# tracker03-09.net
KiCad netlist of a schematic drawn in EAGLE
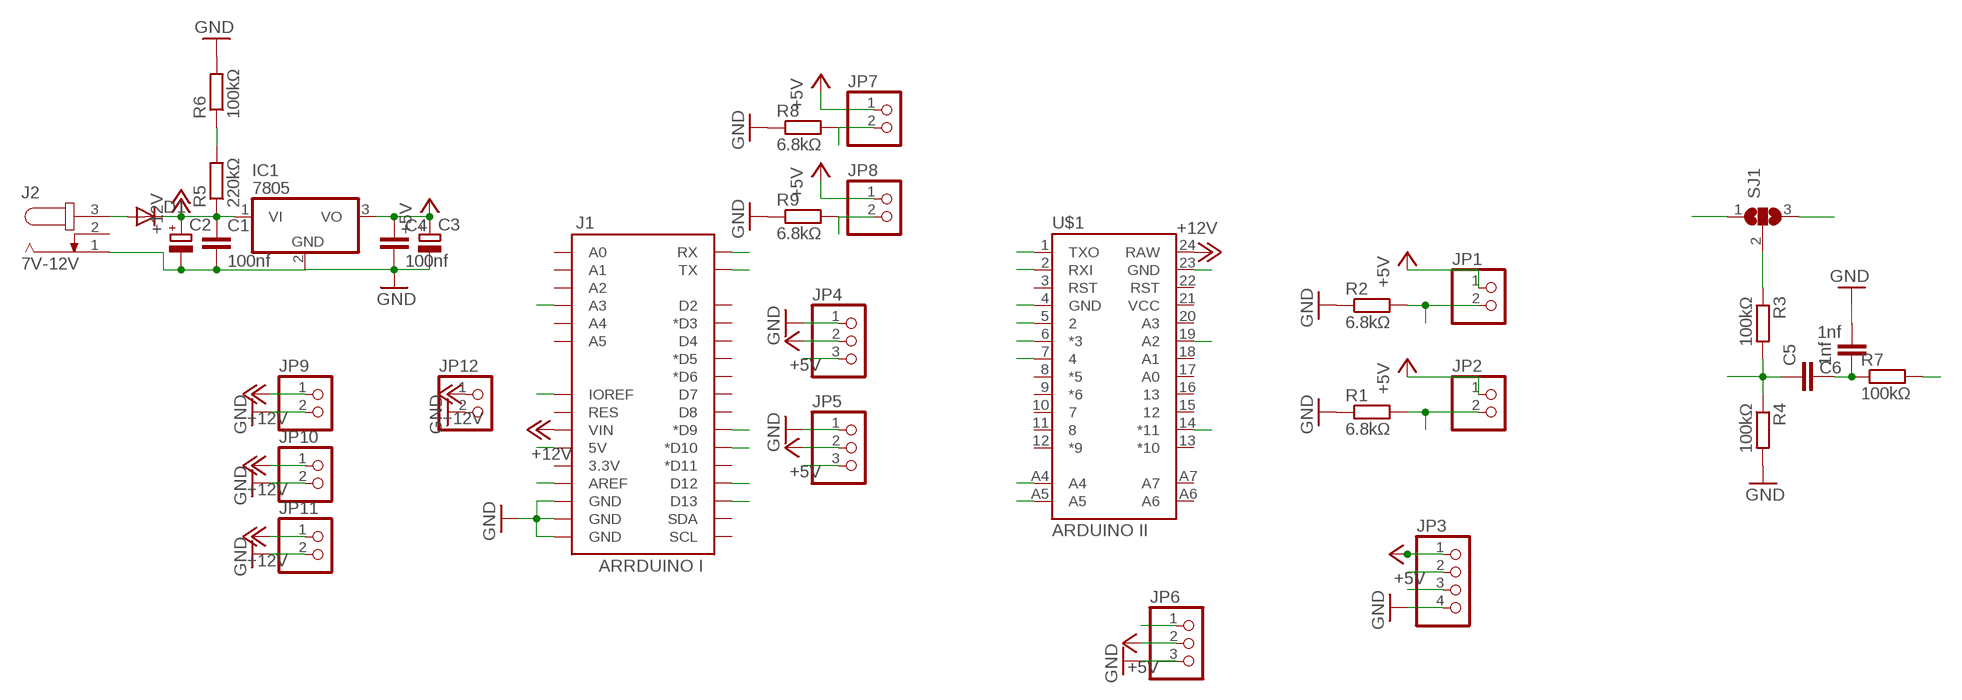
[diagram p0: schematic, sheet 1]

(export (version "E")
  (design (tool "Eeschema 10.0.6"))
  (components
    (comp (ref "C1")
      (value "100nf")
      (footprint "eagle-import:C050-025X075")
      (libsource (lib "eagle-import") (part "C-EU050-025X075"))
    )
    (comp (ref "C2")
      (value "CPOL-EUE3.5-8")
      (footprint "eagle-import:E3,5-8")
      (libsource (lib "eagle-import") (part "CPOL-EUE3.5-8"))
    )
    (comp (ref "C3")
      (value "CPOL-EUE2.5-5")
      (footprint "eagle-import:E2,5-5")
      (libsource (lib "eagle-import") (part "CPOL-EUE2.5-5"))
    )
    (comp (ref "C4")
      (value "100nf")
      (footprint "eagle-import:C050-025X075")
      (libsource (lib "eagle-import") (part "C-EU050-025X075"))
    )
    (comp (ref "C5")
      (value "1nf")
      (footprint "eagle-import:C050-025X075")
      (libsource (lib "eagle-import") (part "C-EU050-025X075"))
    )
    (comp (ref "C6")
      (value "1nf")
      (footprint "eagle-import:C050-025X075")
      (libsource (lib "eagle-import") (part "C-EU050-025X075"))
    )
    (comp (ref "D1")
      (value "1N4004")
      (footprint "eagle-import:DO41-10")
      (libsource (lib "eagle-import") (part "1N4004"))
    )
    (comp (ref "IC1")
      (value "7805")
      (footprint "eagle-import:TO220V")
      (libsource (lib "eagle-import") (part "78TV05"))
    )
    (comp (ref "J1")
      (value "ARRDUINO I")
      (footprint "eagle-import:UNO_R3_SHIELD_NOLABELS")
      (libsource (lib "eagle-import") (part "ARDUINO_R3_SHIELDNOLABELS"))
    )
    (comp (ref "J2")
      (value "7V-12V")
      (footprint "eagle-import:SPC4077")
      (libsource (lib "eagle-import") (part "JACK-PLUG0"))
    )
    (comp (ref "JP1")
      (value "PINHD-1X2")
      (footprint "eagle-import:1X02")
      (libsource (lib "eagle-import") (part "PINHD-1X2"))
    )
    (comp (ref "JP2")
      (value "PINHD-1X2")
      (footprint "eagle-import:1X02")
      (libsource (lib "eagle-import") (part "PINHD-1X2"))
    )
    (comp (ref "JP3")
      (value "PINHD-1X4")
      (footprint "eagle-import:1X04")
      (libsource (lib "eagle-import") (part "PINHD-1X4"))
    )
    (comp (ref "JP4")
      (value "PINHD-1X3")
      (footprint "eagle-import:1X03")
      (libsource (lib "eagle-import") (part "PINHD-1X3"))
    )
    (comp (ref "JP5")
      (value "PINHD-1X3")
      (footprint "eagle-import:1X03")
      (libsource (lib "eagle-import") (part "PINHD-1X3"))
    )
    (comp (ref "JP6")
      (value "PINHD-1X3")
      (footprint "eagle-import:1X03")
      (libsource (lib "eagle-import") (part "PINHD-1X3"))
    )
    (comp (ref "JP7")
      (value "PINHD-1X2")
      (footprint "eagle-import:1X02")
      (libsource (lib "eagle-import") (part "PINHD-1X2"))
    )
    (comp (ref "JP8")
      (value "PINHD-1X2")
      (footprint "eagle-import:1X02")
      (libsource (lib "eagle-import") (part "PINHD-1X2"))
    )
    (comp (ref "JP9")
      (value "PINHD-1X2")
      (footprint "eagle-import:1X02")
      (libsource (lib "eagle-import") (part "PINHD-1X2"))
    )
    (comp (ref "JP10")
      (value "PINHD-1X2")
      (footprint "eagle-import:1X02")
      (libsource (lib "eagle-import") (part "PINHD-1X2"))
    )
    (comp (ref "JP11")
      (value "PINHD-1X2")
      (footprint "eagle-import:1X02")
      (libsource (lib "eagle-import") (part "PINHD-1X2"))
    )
    (comp (ref "JP12")
      (value "PINHD-1X2")
      (footprint "eagle-import:1X02")
      (libsource (lib "eagle-import") (part "PINHD-1X2"))
    )
    (comp (ref "R1")
      (value "6.8kΩ")
      (footprint "eagle-import:0204V")
      (libsource (lib "eagle-import") (part "R-EU_0204/2V"))
    )
    (comp (ref "R2")
      (value "6.8kΩ")
      (footprint "eagle-import:0204V")
      (libsource (lib "eagle-import") (part "R-EU_0204/2V"))
    )
    (comp (ref "R3")
      (value "100kΩ")
      (footprint "eagle-import:0204V")
      (libsource (lib "eagle-import") (part "R-EU_0204/2V"))
    )
    (comp (ref "R4")
      (value "100kΩ")
      (footprint "eagle-import:0204V")
      (libsource (lib "eagle-import") (part "R-EU_0204/2V"))
    )
    (comp (ref "R5")
      (value "220kΩ")
      (footprint "eagle-import:0204V")
      (libsource (lib "eagle-import") (part "R-EU_0204/2V"))
    )
    (comp (ref "R6")
      (value "100kΩ")
      (footprint "eagle-import:0204V")
      (libsource (lib "eagle-import") (part "R-EU_0204/2V"))
    )
    (comp (ref "R7")
      (value "100kΩ")
      (footprint "eagle-import:0204V")
      (libsource (lib "eagle-import") (part "R-EU_0204/2V"))
    )
    (comp (ref "R8")
      (value "6.8kΩ")
      (footprint "eagle-import:0204V")
      (libsource (lib "eagle-import") (part "R-EU_0204/2V"))
    )
    (comp (ref "R9")
      (value "6.8kΩ")
      (footprint "eagle-import:0204V")
      (libsource (lib "eagle-import") (part "R-EU_0204/2V"))
    )
    (comp (ref "SJ1")
      (value "SJ2W")
      (footprint "eagle-import:SJ_2")
      (libsource (lib "eagle-import") (part "SJ2W"))
    )
    (comp (ref "U$1")
      (value "ARDUINO II")
      (footprint "eagle-import:ARDUINO_PRO_MINI")
      (libsource (lib "eagle-import") (part "ARDUINO_PRO_MINI"))
    )
  )
  (nets
    (net (code "1") (name "+5V") (class "Default")
      (node (ref "C3") (pin "+") (pinfunction "+_+") (pintype "passive"))
      (node (ref "C4") (pin "1") (pinfunction "1_1") (pintype "passive"))
      (node (ref "IC1") (pin "3") (pinfunction "VO_3") (pintype "passive"))
      (node (ref "JP1") (pin "1") (pinfunction "1_1") (pintype "passive"))
      (node (ref "JP2") (pin "1") (pinfunction "1_1") (pintype "passive"))
      (node (ref "JP3") (pin "1") (pinfunction "1_1") (pintype "passive"))
      (node (ref "JP4") (pin "2") (pinfunction "2_2") (pintype "passive"))
      (node (ref "JP5") (pin "2") (pinfunction "2_2") (pintype "passive"))
      (node (ref "JP6") (pin "2") (pinfunction "2_2") (pintype "passive"))
      (node (ref "JP7") (pin "1") (pinfunction "1_1") (pintype "passive"))
      (node (ref "JP8") (pin "1") (pinfunction "1_1") (pintype "passive"))
    )
    (net (code "2") (name "+12V") (class "Default")
      (node (ref "C1") (pin "1") (pinfunction "1_1") (pintype "passive"))
      (node (ref "C2") (pin "+") (pinfunction "+_+") (pintype "passive"))
      (node (ref "D1") (pin "C") (pinfunction "C_C") (pintype "passive"))
      (node (ref "IC1") (pin "1") (pinfunction "VI_1") (pintype "input"))
      (node (ref "J1") (pin "VIN") (pinfunction "VIN_VIN") (pintype "bidirectional"))
      (node (ref "JP10") (pin "1") (pinfunction "1_1") (pintype "passive"))
      (node (ref "JP11") (pin "1") (pinfunction "1_1") (pintype "passive"))
      (node (ref "JP12") (pin "1") (pinfunction "1_1") (pintype "passive"))
      (node (ref "JP9") (pin "1") (pinfunction "1_1") (pintype "passive"))
      (node (ref "R5") (pin "1") (pinfunction "1_1") (pintype "passive"))
      (node (ref "U$1") (pin "24") (pinfunction "RAW_24") (pintype "bidirectional"))
    )
    (net (code "3") (name "/5VA") (class "Default")
      (node (ref "J1") (pin "5V") (pinfunction "5V_5V") (pintype "bidirectional"))
      (node (ref "SJ1") (pin "3") (pinfunction "3_3") (pintype "passive"))
    )
    (net (code "4") (name "/A2") (class "Default")
      (node (ref "R5") (pin "2") (pinfunction "2_2") (pintype "passive"))
      (node (ref "R6") (pin "1") (pinfunction "1_1") (pintype "passive"))
      (node (ref "U$1") (pin "19") (pinfunction "A2_19") (pintype "bidirectional"))
    )
    (net (code "5") (name "/A3") (class "Default")
      (node (ref "C5") (pin "1") (pinfunction "1_1") (pintype "passive"))
      (node (ref "J1") (pin "A3") (pinfunction "A3_A3") (pintype "bidirectional"))
      (node (ref "R3") (pin "2") (pinfunction "2_2") (pintype "passive"))
      (node (ref "R4") (pin "1") (pinfunction "1_1") (pintype "passive"))
    )
    (net (code "6") (name "/A4") (class "Default")
      (node (ref "JP3") (pin "2") (pinfunction "2_2") (pintype "passive"))
      (node (ref "U$1") (pin "A4") (pinfunction "A4_A4") (pintype "bidirectional"))
    )
    (net (code "7") (name "/A5") (class "Default")
      (node (ref "JP3") (pin "3") (pinfunction "3_3") (pintype "passive"))
      (node (ref "U$1") (pin "A5") (pinfunction "A5_A5") (pintype "bidirectional"))
    )
    (net (code "8") (name "/AREF") (class "Default")
      (node (ref "J1") (pin "AREF") (pinfunction "AREF_AREF") (pintype "bidirectional"))
      (node (ref "SJ1") (pin "1") (pinfunction "1_1") (pintype "passive"))
    )
    (net (code "9") (name "/D2") (class "Default")
      (node (ref "JP1") (pin "2") (pinfunction "2_2") (pintype "passive"))
      (node (ref "R2") (pin "2") (pinfunction "2_2") (pintype "passive"))
      (node (ref "U$1") (pin "5") (pinfunction "2_5") (pintype "bidirectional"))
    )
    (net (code "10") (name "/D4") (class "Default")
      (node (ref "JP2") (pin "2") (pinfunction "2_2") (pintype "passive"))
      (node (ref "R1") (pin "2") (pinfunction "2_2") (pintype "passive"))
      (node (ref "U$1") (pin "7") (pinfunction "4_7") (pintype "bidirectional"))
    )
    (net (code "11") (name "/D9") (class "Default")
      (node (ref "J1") (pin "D9") (pinfunction "*D9_D9") (pintype "bidirectional"))
      (node (ref "JP4") (pin "3") (pinfunction "3_3") (pintype "passive"))
    )
    (net (code "12") (name "/D10") (class "Default")
      (node (ref "J1") (pin "D10") (pinfunction "*D10_D10") (pintype "bidirectional"))
      (node (ref "JP5") (pin "3") (pinfunction "3_3") (pintype "passive"))
    )
    (net (code "13") (name "/D11") (class "Default")
      (node (ref "JP6") (pin "1") (pinfunction "1_1") (pintype "passive"))
      (node (ref "U$1") (pin "14") (pinfunction "*11_14") (pintype "bidirectional"))
    )
    (net (code "14") (name "/D12") (class "Default")
      (node (ref "J1") (pin "D12") (pinfunction "D12_D12") (pintype "bidirectional"))
      (node (ref "JP7") (pin "2") (pinfunction "2_2") (pintype "passive"))
      (node (ref "R8") (pin "2") (pinfunction "2_2") (pintype "passive"))
    )
    (net (code "15") (name "/D13") (class "Default")
      (node (ref "J1") (pin "D13") (pinfunction "D13_D13") (pintype "bidirectional"))
      (node (ref "JP8") (pin "2") (pinfunction "2_2") (pintype "passive"))
      (node (ref "R9") (pin "2") (pinfunction "2_2") (pintype "passive"))
    )
    (net (code "16") (name "/RX") (class "Default")
      (node (ref "J1") (pin "RX") (pinfunction "RX_RX") (pintype "bidirectional"))
      (node (ref "U$1") (pin "1") (pinfunction "TXO_1") (pintype "bidirectional"))
    )
    (net (code "17") (name "/TX") (class "Default")
      (node (ref "J1") (pin "TX") (pinfunction "TX_TX") (pintype "bidirectional"))
      (node (ref "U$1") (pin "2") (pinfunction "RXI_2") (pintype "bidirectional"))
    )
    (net (code "18") (name "GND") (class "Default")
      (node (ref "C1") (pin "2") (pinfunction "2_2") (pintype "passive"))
      (node (ref "C2") (pin "-") (pinfunction "-_-") (pintype "passive"))
      (node (ref "C3") (pin "-") (pinfunction "-_-") (pintype "passive"))
      (node (ref "C4") (pin "2") (pinfunction "2_2") (pintype "passive"))
      (node (ref "C6") (pin "2") (pinfunction "2_2") (pintype "passive"))
      (node (ref "IC1") (pin "2") (pinfunction "GND_2") (pintype "passive"))
      (node (ref "J1") (pin "GND@0") (pinfunction "GND_GND@0") (pintype "bidirectional"))
      (node (ref "J1") (pin "GND@1") (pinfunction "GND_GND@1") (pintype "bidirectional"))
      (node (ref "J1") (pin "GND@2") (pinfunction "GND_GND@2") (pintype "bidirectional"))
      (node (ref "J2") (pin "1") (pinfunction "1_1") (pintype "passive"))
      (node (ref "JP10") (pin "2") (pinfunction "2_2") (pintype "passive"))
      (node (ref "JP11") (pin "2") (pinfunction "2_2") (pintype "passive"))
      (node (ref "JP12") (pin "2") (pinfunction "2_2") (pintype "passive"))
      (node (ref "JP3") (pin "4") (pinfunction "4_4") (pintype "passive"))
      (node (ref "JP4") (pin "1") (pinfunction "1_1") (pintype "passive"))
      (node (ref "JP5") (pin "1") (pinfunction "1_1") (pintype "passive"))
      (node (ref "JP6") (pin "3") (pinfunction "3_3") (pintype "passive"))
      (node (ref "JP9") (pin "2") (pinfunction "2_2") (pintype "passive"))
      (node (ref "R1") (pin "1") (pinfunction "1_1") (pintype "passive"))
      (node (ref "R2") (pin "1") (pinfunction "1_1") (pintype "passive"))
      (node (ref "R4") (pin "2") (pinfunction "2_2") (pintype "passive"))
      (node (ref "R6") (pin "2") (pinfunction "2_2") (pintype "passive"))
      (node (ref "R8") (pin "1") (pinfunction "1_1") (pintype "passive"))
      (node (ref "R9") (pin "1") (pinfunction "1_1") (pintype "passive"))
      (node (ref "U$1") (pin "23") (pinfunction "GND_23") (pintype "bidirectional"))
      (node (ref "U$1") (pin "4") (pinfunction "GND_4") (pintype "bidirectional"))
    )
    (net (code "19") (name "Net-(C5-Pad2)") (class "Default")
      (node (ref "C5") (pin "2") (pinfunction "2_2") (pintype "passive"))
      (node (ref "C6") (pin "1") (pinfunction "1_1") (pintype "passive"))
      (node (ref "R7") (pin "1") (pinfunction "1_1") (pintype "passive"))
    )
    (net (code "20") (name "Net-(D1-PadA)") (class "Default")
      (node (ref "D1") (pin "A") (pinfunction "A_A") (pintype "passive"))
      (node (ref "J2") (pin "3") (pinfunction "3_3") (pintype "passive"))
    )
    (net (code "21") (name "Net-(R3-Pad1)") (class "Default")
      (node (ref "R3") (pin "1") (pinfunction "1_1") (pintype "passive"))
      (node (ref "SJ1") (pin "2") (pinfunction "2_2") (pintype "passive"))
    )
    (net (code "22") (name "unconnected-(J1-*D3-PadD3)") (class "Default")
      (node (ref "J1") (pin "D3") (pinfunction "*D3_D3") (pintype "bidirectional"))
    )
    (net (code "23") (name "unconnected-(J1-*D5-PadD5)") (class "Default")
      (node (ref "J1") (pin "D5") (pinfunction "*D5_D5") (pintype "bidirectional"))
    )
    (net (code "24") (name "unconnected-(J1-*D6-PadD6)") (class "Default")
      (node (ref "J1") (pin "D6") (pinfunction "*D6_D6") (pintype "bidirectional"))
    )
    (net (code "25") (name "unconnected-(J1-*D11-PadD11)") (class "Default")
      (node (ref "J1") (pin "D11") (pinfunction "*D11_D11") (pintype "bidirectional"))
    )
    (net (code "26") (name "unconnected-(J1-Pad3.3V)") (class "Default")
      (node (ref "J1") (pin "3.3V") (pinfunction "3.3V_3.3V") (pintype "bidirectional"))
    )
    (net (code "27") (name "unconnected-(J1-PadA0)") (class "Default")
      (node (ref "J1") (pin "A0") (pinfunction "A0_A0") (pintype "bidirectional"))
    )
    (net (code "28") (name "unconnected-(J1-PadA1)") (class "Default")
      (node (ref "J1") (pin "A1") (pinfunction "A1_A1") (pintype "bidirectional"))
    )
    (net (code "29") (name "unconnected-(J1-PadA2)") (class "Default")
      (node (ref "J1") (pin "A2") (pinfunction "A2_A2") (pintype "bidirectional"))
    )
    (net (code "30") (name "unconnected-(J1-PadA4)") (class "Default")
      (node (ref "J1") (pin "A4") (pinfunction "A4_A4") (pintype "bidirectional"))
    )
    (net (code "31") (name "unconnected-(J1-PadA5)") (class "Default")
      (node (ref "J1") (pin "A5") (pinfunction "A5_A5") (pintype "bidirectional"))
    )
    (net (code "32") (name "unconnected-(J1-PadD2)") (class "Default")
      (node (ref "J1") (pin "D2") (pinfunction "D2_D2") (pintype "bidirectional"))
    )
    (net (code "33") (name "unconnected-(J1-PadD4)") (class "Default")
      (node (ref "J1") (pin "D4") (pinfunction "D4_D4") (pintype "bidirectional"))
    )
    (net (code "34") (name "unconnected-(J1-PadD7)") (class "Default")
      (node (ref "J1") (pin "D7") (pinfunction "D7_D7") (pintype "bidirectional"))
    )
    (net (code "35") (name "unconnected-(J1-PadD8)") (class "Default")
      (node (ref "J1") (pin "D8") (pinfunction "D8_D8") (pintype "bidirectional"))
    )
    (net (code "36") (name "unconnected-(J1-PadIOREF)") (class "Default")
      (node (ref "J1") (pin "IOREF") (pinfunction "IOREF_IOREF") (pintype "bidirectional"))
    )
    (net (code "37") (name "unconnected-(J1-PadRES)") (class "Default")
      (node (ref "J1") (pin "RES") (pinfunction "RES_RES") (pintype "bidirectional"))
    )
    (net (code "38") (name "unconnected-(J1-PadSCL)") (class "Default")
      (node (ref "J1") (pin "SCL") (pinfunction "SCL_SCL") (pintype "bidirectional"))
    )
    (net (code "39") (name "unconnected-(J1-PadSDA)") (class "Default")
      (node (ref "J1") (pin "SDA") (pinfunction "SDA_SDA") (pintype "bidirectional"))
    )
    (net (code "40") (name "unconnected-(J2-Pad2)") (class "Default")
      (node (ref "J2") (pin "2") (pinfunction "2_2") (pintype "passive"))
    )
    (net (code "41") (name "unconnected-(R7-Pad2)") (class "Default")
      (node (ref "R7") (pin "2") (pinfunction "2_2") (pintype "passive"))
    )
    (net (code "42") (name "unconnected-(U$1-*3-Pad6)") (class "Default")
      (node (ref "U$1") (pin "6") (pinfunction "*3_6") (pintype "bidirectional"))
    )
    (net (code "43") (name "unconnected-(U$1-*5-Pad8)") (class "Default")
      (node (ref "U$1") (pin "8") (pinfunction "*5_8") (pintype "bidirectional"))
    )
    (net (code "44") (name "unconnected-(U$1-*6-Pad9)") (class "Default")
      (node (ref "U$1") (pin "9") (pinfunction "*6_9") (pintype "bidirectional"))
    )
    (net (code "45") (name "unconnected-(U$1-*9-Pad12)") (class "Default")
      (node (ref "U$1") (pin "12") (pinfunction "*9_12") (pintype "bidirectional"))
    )
    (net (code "46") (name "unconnected-(U$1-*10-Pad13)") (class "Default")
      (node (ref "U$1") (pin "13") (pinfunction "*10_13") (pintype "bidirectional"))
    )
    (net (code "47") (name "unconnected-(U$1-7-Pad10)") (class "Default")
      (node (ref "U$1") (pin "10") (pinfunction "7_10") (pintype "bidirectional"))
    )
    (net (code "48") (name "unconnected-(U$1-8-Pad11)") (class "Default")
      (node (ref "U$1") (pin "11") (pinfunction "8_11") (pintype "bidirectional"))
    )
    (net (code "49") (name "unconnected-(U$1-12-Pad15)") (class "Default")
      (node (ref "U$1") (pin "15") (pinfunction "12_15") (pintype "bidirectional"))
    )
    (net (code "50") (name "unconnected-(U$1-13-Pad16)") (class "Default")
      (node (ref "U$1") (pin "16") (pinfunction "13_16") (pintype "bidirectional"))
    )
    (net (code "51") (name "unconnected-(U$1-A0-Pad17)") (class "Default")
      (node (ref "U$1") (pin "17") (pinfunction "A0_17") (pintype "bidirectional"))
    )
    (net (code "52") (name "unconnected-(U$1-A1-Pad18)") (class "Default")
      (node (ref "U$1") (pin "18") (pinfunction "A1_18") (pintype "bidirectional"))
    )
    (net (code "53") (name "unconnected-(U$1-A3-Pad20)") (class "Default")
      (node (ref "U$1") (pin "20") (pinfunction "A3_20") (pintype "bidirectional"))
    )
    (net (code "54") (name "unconnected-(U$1-PadA6)") (class "Default")
      (node (ref "U$1") (pin "A6") (pinfunction "A6_A6") (pintype "bidirectional"))
    )
    (net (code "55") (name "unconnected-(U$1-PadA7)") (class "Default")
      (node (ref "U$1") (pin "A7") (pinfunction "A7_A7") (pintype "bidirectional"))
    )
    (net (code "56") (name "unconnected-(U$1-RST-Pad3)") (class "Default")
      (node (ref "U$1") (pin "3") (pinfunction "RST_3") (pintype "bidirectional"))
    )
    (net (code "57") (name "unconnected-(U$1-RST-Pad22)") (class "Default")
      (node (ref "U$1") (pin "22") (pinfunction "RST_22") (pintype "bidirectional"))
    )
    (net (code "58") (name "unconnected-(U$1-VCC-Pad21)") (class "Default")
      (node (ref "U$1") (pin "21") (pinfunction "VCC_21") (pintype "bidirectional"))
    )
  )
)
